# a917-stereo-split.net
KiCad netlist of a schematic drawn in EAGLE
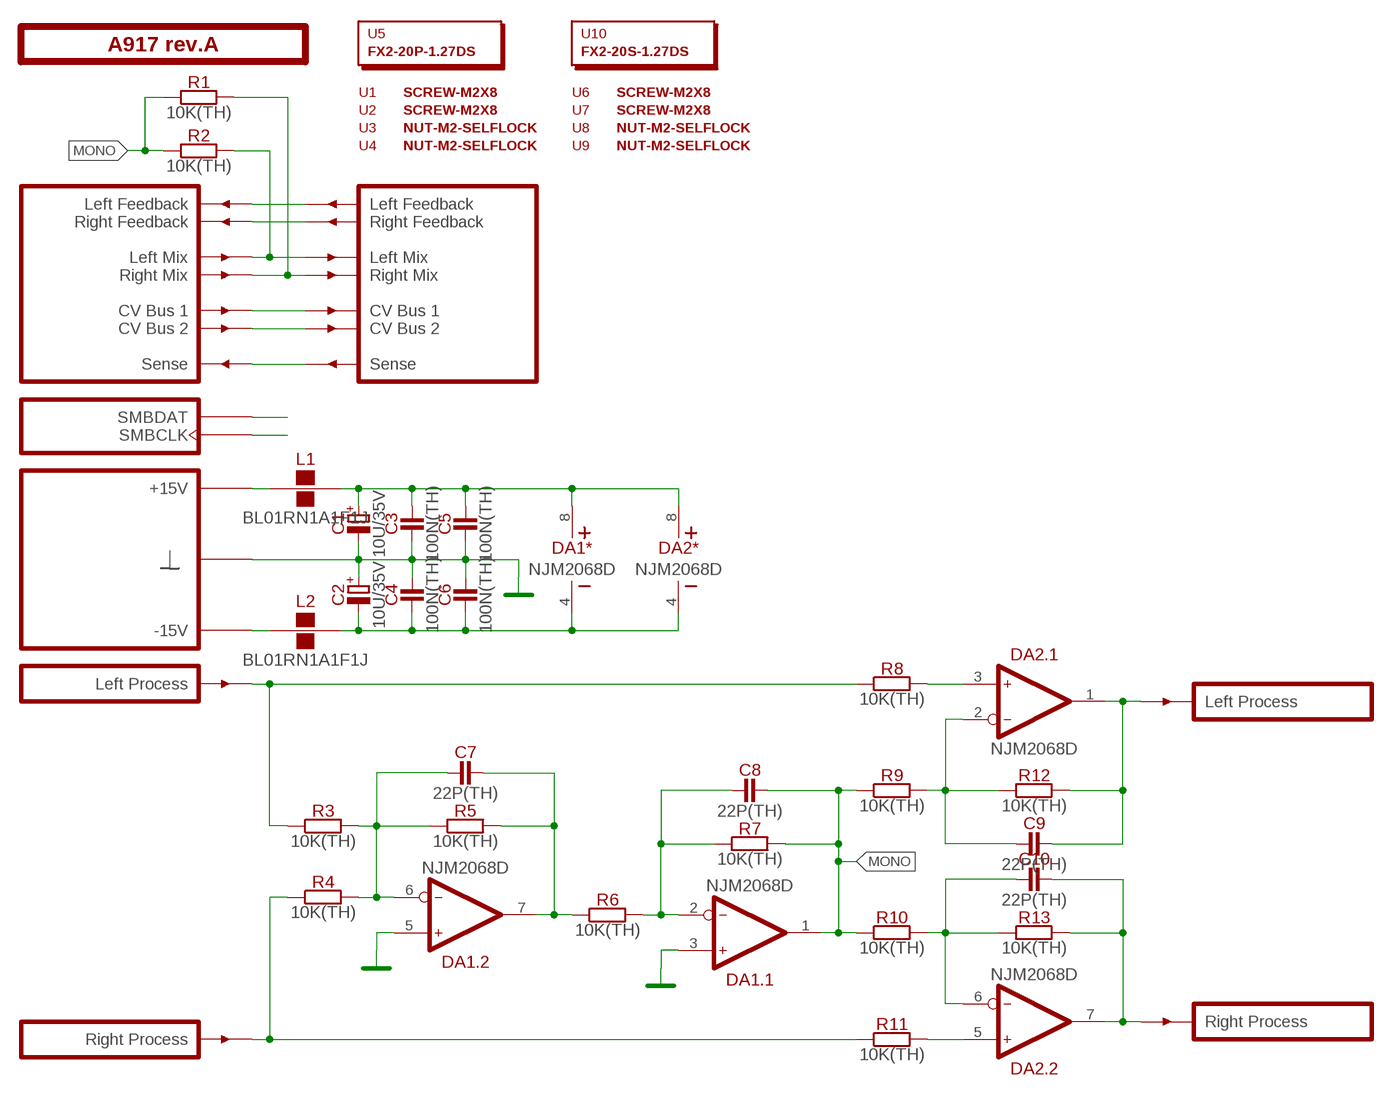
[diagram p0: schematic, sheet 1]

(export (version "E")
  (design (tool "Eeschema 10.0.6"))
  (components
    (comp (ref "C1")
      (value "10U/35V")
      (footprint "eagle-import:E2-5")
      (libsource (lib "eagle-import") (part "?10U/35V"))
    )
    (comp (ref "C2")
      (value "10U/35V")
      (footprint "eagle-import:E2-5")
      (libsource (lib "eagle-import") (part "?10U/35V"))
    )
    (comp (ref "C3")
      (value "100N(TH)")
      (footprint "eagle-import:C050-024X044")
      (libsource (lib "eagle-import") (part "?100N(TH)"))
    )
    (comp (ref "C4")
      (value "100N(TH)")
      (footprint "eagle-import:C050-024X044")
      (libsource (lib "eagle-import") (part "?100N(TH)"))
    )
    (comp (ref "C5")
      (value "100N(TH)")
      (footprint "eagle-import:C050-024X044")
      (libsource (lib "eagle-import") (part "?100N(TH)"))
    )
    (comp (ref "C6")
      (value "100N(TH)")
      (footprint "eagle-import:C050-024X044")
      (libsource (lib "eagle-import") (part "?100N(TH)"))
    )
    (comp (ref "C7")
      (value "22P(TH)")
      (footprint "eagle-import:C050-024X044")
      (libsource (lib "eagle-import") (part "?22P(TH)"))
    )
    (comp (ref "C8")
      (value "22P(TH)")
      (footprint "eagle-import:C050-024X044")
      (libsource (lib "eagle-import") (part "?22P(TH)"))
    )
    (comp (ref "C9")
      (value "22P(TH)")
      (footprint "eagle-import:C050-024X044")
      (libsource (lib "eagle-import") (part "?22P(TH)"))
    )
    (comp (ref "C10")
      (value "22P(TH)")
      (footprint "eagle-import:C050-024X044")
      (libsource (lib "eagle-import") (part "?22P(TH)"))
    )
    (comp (ref "DA1")
      (value "NJM2068D")
      (footprint "eagle-import:DIP-8")
      (libsource (lib "eagle-import") (part "NJM2068D"))
    )
    (comp (ref "DA2")
      (value "NJM2068D")
      (footprint "eagle-import:DIP-8")
      (libsource (lib "eagle-import") (part "NJM2068D"))
    )
    (comp (ref "L1")
      (value "BL01RN1A1F1J")
      (footprint "eagle-import:BL01RN1A")
      (libsource (lib "eagle-import") (part "BL01RN1A?1F1J"))
    )
    (comp (ref "L2")
      (value "BL01RN1A1F1J")
      (footprint "eagle-import:BL01RN1A")
      (libsource (lib "eagle-import") (part "BL01RN1A?1F1J"))
    )
    (comp (ref "PCB1")
      (value "A917 rev.A")
      (footprint "eagle-import:ST2-BOARD-26")
      (libsource (lib "eagle-import") (part "ST2-BOARD-?26"))
    )
    (comp (ref "R1")
      (value "10K(TH)")
      (footprint "eagle-import:R-0207_10")
      (libsource (lib "eagle-import") (part "?10K(TH)"))
    )
    (comp (ref "R2")
      (value "10K(TH)")
      (footprint "eagle-import:R-0207_10")
      (libsource (lib "eagle-import") (part "?10K(TH)"))
    )
    (comp (ref "R3")
      (value "10K(TH)")
      (footprint "eagle-import:R-0207_10")
      (libsource (lib "eagle-import") (part "?10K(TH)"))
    )
    (comp (ref "R4")
      (value "10K(TH)")
      (footprint "eagle-import:R-0207_10")
      (libsource (lib "eagle-import") (part "?10K(TH)"))
    )
    (comp (ref "R5")
      (value "10K(TH)")
      (footprint "eagle-import:R-0207_10")
      (libsource (lib "eagle-import") (part "?10K(TH)"))
    )
    (comp (ref "R6")
      (value "10K(TH)")
      (footprint "eagle-import:R-0207_10")
      (libsource (lib "eagle-import") (part "?10K(TH)"))
    )
    (comp (ref "R7")
      (value "10K(TH)")
      (footprint "eagle-import:R-0207_10")
      (libsource (lib "eagle-import") (part "?10K(TH)"))
    )
    (comp (ref "R8")
      (value "10K(TH)")
      (footprint "eagle-import:R-0207_10")
      (libsource (lib "eagle-import") (part "?10K(TH)"))
    )
    (comp (ref "R9")
      (value "10K(TH)")
      (footprint "eagle-import:R-0207_10")
      (libsource (lib "eagle-import") (part "?10K(TH)"))
    )
    (comp (ref "R10")
      (value "10K(TH)")
      (footprint "eagle-import:R-0207_10")
      (libsource (lib "eagle-import") (part "?10K(TH)"))
    )
    (comp (ref "R11")
      (value "10K(TH)")
      (footprint "eagle-import:R-0207_10")
      (libsource (lib "eagle-import") (part "?10K(TH)"))
    )
    (comp (ref "R12")
      (value "10K(TH)")
      (footprint "eagle-import:R-0207_10")
      (libsource (lib "eagle-import") (part "?10K(TH)"))
    )
    (comp (ref "R13")
      (value "10K(TH)")
      (footprint "eagle-import:R-0207_10")
      (libsource (lib "eagle-import") (part "?10K(TH)"))
    )
    (comp (ref "U1")
      (value "SCREW-M2X8")
      (footprint "eagle-import:EMPTY")
      (libsource (lib "eagle-import") (part "?SCREW-M2X8"))
    )
    (comp (ref "U2")
      (value "SCREW-M2X8")
      (footprint "eagle-import:EMPTY")
      (libsource (lib "eagle-import") (part "?SCREW-M2X8"))
    )
    (comp (ref "U3")
      (value "NUT-M2-SELFLOCK")
      (footprint "eagle-import:EMPTY")
      (libsource (lib "eagle-import") (part "?NUT-M2-SELFLOCK"))
    )
    (comp (ref "U4")
      (value "NUT-M2-SELFLOCK")
      (footprint "eagle-import:EMPTY")
      (libsource (lib "eagle-import") (part "?NUT-M2-SELFLOCK"))
    )
    (comp (ref "U5")
      (value "FX2-20P-1.27DS")
      (footprint "eagle-import:EMPTY")
      (libsource (lib "eagle-import") (part "?FX2-20P-1.27DS"))
    )
    (comp (ref "U6")
      (value "SCREW-M2X8")
      (footprint "eagle-import:EMPTY")
      (libsource (lib "eagle-import") (part "?SCREW-M2X8"))
    )
    (comp (ref "U7")
      (value "SCREW-M2X8")
      (footprint "eagle-import:EMPTY")
      (libsource (lib "eagle-import") (part "?SCREW-M2X8"))
    )
    (comp (ref "U8")
      (value "NUT-M2-SELFLOCK")
      (footprint "eagle-import:EMPTY")
      (libsource (lib "eagle-import") (part "?NUT-M2-SELFLOCK"))
    )
    (comp (ref "U9")
      (value "NUT-M2-SELFLOCK")
      (footprint "eagle-import:EMPTY")
      (libsource (lib "eagle-import") (part "?NUT-M2-SELFLOCK"))
    )
    (comp (ref "U10")
      (value "FX2-20S-1.27DS")
      (footprint "eagle-import:EMPTY")
      (libsource (lib "eagle-import") (part "?FX2-20S-1.27DS"))
    )
  )
  (nets
    (net (code "1") (name "GND") (class "Default")
      (node (ref "C1") (pin "-") (pinfunction "-_-") (pintype "passive"))
      (node (ref "C2") (pin "+") (pinfunction "+_+") (pintype "passive"))
      (node (ref "C3") (pin "1") (pinfunction "1_1") (pintype "passive"))
      (node (ref "C4") (pin "2") (pinfunction "2_2") (pintype "passive"))
      (node (ref "C5") (pin "1") (pinfunction "1_1") (pintype "passive"))
      (node (ref "C6") (pin "2") (pinfunction "2_2") (pintype "passive"))
      (node (ref "DA1") (pin "3") (pinfunction "IN+_3") (pintype "input"))
      (node (ref "DA1") (pin "5") (pinfunction "IN+_5") (pintype "input"))
      (node (ref "PCB1") (pin "B4") (pinfunction "GND_B4") (pintype "bidirectional"))
      (node (ref "PCB1") (pin "B4'") (pinfunction "GND_B4'") (pintype "bidirectional"))
      (node (ref "PCB1") (pin "B5") (pinfunction "GND_B5") (pintype "bidirectional"))
      (node (ref "PCB1") (pin "B5'") (pinfunction "GND_B5'") (pintype "bidirectional"))
      (node (ref "PCB1") (pin "B6") (pinfunction "GND_B6") (pintype "bidirectional"))
      (node (ref "PCB1") (pin "B6'") (pinfunction "GND_B6'") (pintype "bidirectional"))
      (node (ref "PCB1") (pin "B7") (pinfunction "GND_B7") (pintype "bidirectional"))
      (node (ref "PCB1") (pin "B7'") (pinfunction "GND_B7'") (pintype "bidirectional"))
      (node (ref "PCB1") (pin "B8") (pinfunction "GND_B8") (pintype "bidirectional"))
      (node (ref "PCB1") (pin "B8'") (pinfunction "GND_B8'") (pintype "bidirectional"))
    )
    (net (code "2") (name "MONO") (class "Default")
      (node (ref "C8") (pin "2") (pinfunction "2_2") (pintype "passive"))
      (node (ref "DA1") (pin "1") (pinfunction "OUT_1") (pintype "output"))
      (node (ref "R1") (pin "1") (pinfunction "1_1") (pintype "passive"))
      (node (ref "R10") (pin "1") (pinfunction "1_1") (pintype "passive"))
      (node (ref "R2") (pin "1") (pinfunction "1_1") (pintype "passive"))
      (node (ref "R7") (pin "2") (pinfunction "2_2") (pintype "passive"))
      (node (ref "R9") (pin "1") (pinfunction "1_1") (pintype "passive"))
    )
    (net (code "3") (name "Net-(DA1A-V+)") (class "Default")
      (node (ref "C1") (pin "+") (pinfunction "+_+") (pintype "passive"))
      (node (ref "C3") (pin "2") (pinfunction "2_2") (pintype "passive"))
      (node (ref "C5") (pin "2") (pinfunction "2_2") (pintype "passive"))
      (node (ref "DA1") (pin "8") (pinfunction "V+_8") (pintype "power_in"))
      (node (ref "DA2") (pin "8") (pinfunction "V+_8") (pintype "power_in"))
      (node (ref "L1") (pin "2") (pinfunction "2_2") (pintype "passive"))
    )
    (net (code "4") (name "Net-(DA1A-V-)") (class "Default")
      (node (ref "C2") (pin "-") (pinfunction "-_-") (pintype "passive"))
      (node (ref "C4") (pin "1") (pinfunction "1_1") (pintype "passive"))
      (node (ref "C6") (pin "1") (pinfunction "1_1") (pintype "passive"))
      (node (ref "DA1") (pin "4") (pinfunction "V-_4") (pintype "power_in"))
      (node (ref "DA2") (pin "4") (pinfunction "V-_4") (pintype "power_in"))
      (node (ref "L2") (pin "2") (pinfunction "2_2") (pintype "passive"))
    )
    (net (code "5") (name "Net-(DA1B-IN-)") (class "Default")
      (node (ref "C8") (pin "1") (pinfunction "1_1") (pintype "passive"))
      (node (ref "DA1") (pin "2") (pinfunction "IN-_2") (pintype "input"))
      (node (ref "R6") (pin "2") (pinfunction "2_2") (pintype "passive"))
      (node (ref "R7") (pin "1") (pinfunction "1_1") (pintype "passive"))
    )
    (net (code "6") (name "Net-(DA1C-IN-)") (class "Default")
      (node (ref "C7") (pin "1") (pinfunction "1_1") (pintype "passive"))
      (node (ref "DA1") (pin "6") (pinfunction "IN-_6") (pintype "input"))
      (node (ref "R3") (pin "2") (pinfunction "2_2") (pintype "passive"))
      (node (ref "R4") (pin "2") (pinfunction "2_2") (pintype "passive"))
      (node (ref "R5") (pin "1") (pinfunction "1_1") (pintype "passive"))
    )
    (net (code "7") (name "Net-(DA1C-OUT)") (class "Default")
      (node (ref "C7") (pin "2") (pinfunction "2_2") (pintype "passive"))
      (node (ref "DA1") (pin "7") (pinfunction "OUT_7") (pintype "output"))
      (node (ref "R5") (pin "2") (pinfunction "2_2") (pintype "passive"))
      (node (ref "R6") (pin "1") (pinfunction "1_1") (pintype "passive"))
    )
    (net (code "8") (name "Net-(DA2B-IN+)") (class "Default")
      (node (ref "DA2") (pin "3") (pinfunction "IN+_3") (pintype "input"))
      (node (ref "R8") (pin "2") (pinfunction "2_2") (pintype "passive"))
    )
    (net (code "9") (name "Net-(DA2B-IN-)") (class "Default")
      (node (ref "C9") (pin "1") (pinfunction "1_1") (pintype "passive"))
      (node (ref "DA2") (pin "2") (pinfunction "IN-_2") (pintype "input"))
      (node (ref "R12") (pin "1") (pinfunction "1_1") (pintype "passive"))
      (node (ref "R9") (pin "2") (pinfunction "2_2") (pintype "passive"))
    )
    (net (code "10") (name "Net-(DA2B-OUT)") (class "Default")
      (node (ref "C9") (pin "2") (pinfunction "2_2") (pintype "passive"))
      (node (ref "DA2") (pin "1") (pinfunction "OUT_1") (pintype "output"))
      (node (ref "PCB1") (pin "BOUTL'") (pinfunction "OUTL_BOUTL'") (pintype "bidirectional"))
      (node (ref "R12") (pin "2") (pinfunction "2_2") (pintype "passive"))
    )
    (net (code "11") (name "Net-(DA2C-IN+)") (class "Default")
      (node (ref "DA2") (pin "5") (pinfunction "IN+_5") (pintype "input"))
      (node (ref "R11") (pin "2") (pinfunction "2_2") (pintype "passive"))
    )
    (net (code "12") (name "Net-(DA2C-IN-)") (class "Default")
      (node (ref "C10") (pin "1") (pinfunction "1_1") (pintype "passive"))
      (node (ref "DA2") (pin "6") (pinfunction "IN-_6") (pintype "input"))
      (node (ref "R10") (pin "2") (pinfunction "2_2") (pintype "passive"))
      (node (ref "R13") (pin "1") (pinfunction "1_1") (pintype "passive"))
    )
    (net (code "13") (name "Net-(DA2C-OUT)") (class "Default")
      (node (ref "C10") (pin "2") (pinfunction "2_2") (pintype "passive"))
      (node (ref "DA2") (pin "7") (pinfunction "OUT_7") (pintype "output"))
      (node (ref "PCB1") (pin "BOUTR'") (pinfunction "OUTR_BOUTR'") (pintype "bidirectional"))
      (node (ref "R13") (pin "2") (pinfunction "2_2") (pintype "passive"))
    )
    (net (code "14") (name "Net-(L1-Pad1)") (class "Default")
      (node (ref "L1") (pin "1") (pinfunction "1_1") (pintype "passive"))
      (node (ref "PCB1") (pin "A+15") (pinfunction "P+15V_A+15") (pintype "bidirectional"))
      (node (ref "PCB1") (pin "A+15'") (pinfunction "P+15V_A+15'") (pintype "bidirectional"))
      (node (ref "PCB1") (pin "B+15") (pinfunction "P+15V_B+15") (pintype "bidirectional"))
      (node (ref "PCB1") (pin "B+15'") (pinfunction "P+15V_B+15'") (pintype "bidirectional"))
    )
    (net (code "15") (name "Net-(L2-Pad1)") (class "Default")
      (node (ref "L2") (pin "1") (pinfunction "1_1") (pintype "passive"))
      (node (ref "PCB1") (pin "A-15") (pinfunction "P-15V_A-15") (pintype "bidirectional"))
      (node (ref "PCB1") (pin "A-15'") (pinfunction "P-15V_A-15'") (pintype "bidirectional"))
      (node (ref "PCB1") (pin "B-15") (pinfunction "P-15V_B-15") (pintype "bidirectional"))
      (node (ref "PCB1") (pin "B-15'") (pinfunction "P-15V_B-15'") (pintype "bidirectional"))
    )
    (net (code "16") (name "Net-(PCB1B-INL)") (class "Default")
      (node (ref "PCB1") (pin "BINL") (pinfunction "INL_BINL") (pintype "bidirectional"))
      (node (ref "R3") (pin "1") (pinfunction "1_1") (pintype "passive"))
      (node (ref "R8") (pin "1") (pinfunction "1_1") (pintype "passive"))
    )
    (net (code "17") (name "Net-(PCB1C-INR)") (class "Default")
      (node (ref "PCB1") (pin "BINR") (pinfunction "INR_BINR") (pintype "bidirectional"))
      (node (ref "R11") (pin "1") (pinfunction "1_1") (pintype "passive"))
      (node (ref "R4") (pin "1") (pinfunction "1_1") (pintype "passive"))
    )
    (net (code "18") (name "Net-(PCB1F-CV1)") (class "Default")
      (node (ref "PCB1") (pin "ACV1") (pinfunction "CV1_ACV1") (pintype "bidirectional"))
      (node (ref "PCB1") (pin "ACV1'") (pinfunction "CV1'_ACV1'") (pintype "bidirectional"))
    )
    (net (code "19") (name "Net-(PCB1F-CV2)") (class "Default")
      (node (ref "PCB1") (pin "ACV2") (pinfunction "CV2_ACV2") (pintype "bidirectional"))
      (node (ref "PCB1") (pin "ACV2'") (pinfunction "CV2'_ACV2'") (pintype "bidirectional"))
    )
    (net (code "20") (name "Net-(PCB1F-LFBK)") (class "Default")
      (node (ref "PCB1") (pin "ALFBK") (pinfunction "LFBK_ALFBK") (pintype "bidirectional"))
      (node (ref "PCB1") (pin "ALFBK'") (pinfunction "LFBK'_ALFBK'") (pintype "bidirectional"))
    )
    (net (code "21") (name "Net-(PCB1F-LMIX)") (class "Default")
      (node (ref "PCB1") (pin "ALMIX") (pinfunction "LMIX_ALMIX") (pintype "bidirectional"))
      (node (ref "PCB1") (pin "ALMIX'") (pinfunction "LMIX'_ALMIX'") (pintype "bidirectional"))
      (node (ref "R2") (pin "2") (pinfunction "2_2") (pintype "passive"))
    )
    (net (code "22") (name "Net-(PCB1F-RFBK)") (class "Default")
      (node (ref "PCB1") (pin "ARFBK") (pinfunction "RFBK_ARFBK") (pintype "bidirectional"))
      (node (ref "PCB1") (pin "ARFBK'") (pinfunction "RFBK'_ARFBK'") (pintype "bidirectional"))
    )
    (net (code "23") (name "Net-(PCB1F-RMIX)") (class "Default")
      (node (ref "PCB1") (pin "ARMIX") (pinfunction "RMIX_ARMIX") (pintype "bidirectional"))
      (node (ref "PCB1") (pin "ARMIX'") (pinfunction "RMIX'_ARMIX'") (pintype "bidirectional"))
      (node (ref "R1") (pin "2") (pinfunction "2_2") (pintype "passive"))
    )
    (net (code "24") (name "Net-(PCB1F-SENSE)") (class "Default")
      (node (ref "PCB1") (pin "BSENSE") (pinfunction "SENSE_BSENSE") (pintype "bidirectional"))
      (node (ref "PCB1") (pin "BSENSE'") (pinfunction "SENSE'_BSENSE'") (pintype "bidirectional"))
    )
    (net (code "25") (name "Net-(PCB1H-SMBCLK-PadASMBCLK')") (class "Default")
      (node (ref "PCB1") (pin "ASMBCLK") (pinfunction "SMBCLK_ASMBCLK") (pintype "bidirectional"))
      (node (ref "PCB1") (pin "ASMBCLK'") (pinfunction "SMBCLK_ASMBCLK'") (pintype "bidirectional"))
    )
    (net (code "26") (name "Net-(PCB1H-SMBDAT-PadASMBDAT')") (class "Default")
      (node (ref "PCB1") (pin "ASMBDAT") (pinfunction "SMBDAT_ASMBDAT") (pintype "bidirectional"))
      (node (ref "PCB1") (pin "ASMBDAT'") (pinfunction "SMBDAT_ASMBDAT'") (pintype "bidirectional"))
    )
  )
)
